# Face_PCB_Power___I2C.net
KiCad netlist of a schematic drawn in Altium Designer
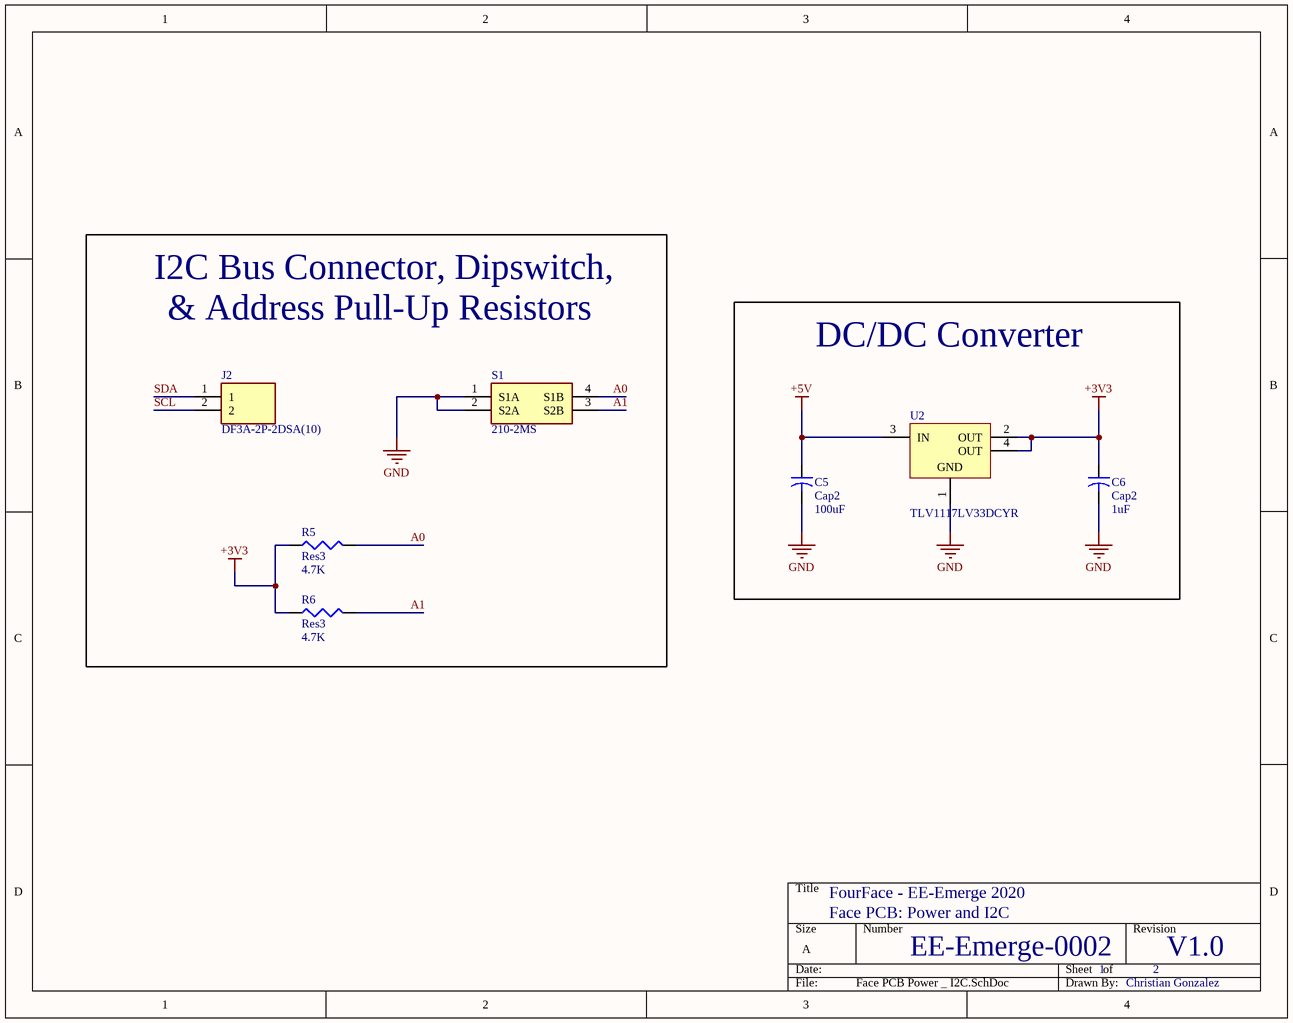
[diagram p0: Face PCB Power _ I2C.SchDoc]

(export (version "E")
  (design (tool "Eeschema 10.0.6"))
  (components
    (comp (ref "C5")
      (value "Cap2")
      (footprint "C0805")
      (description "Capacitor")
      (fields (field (name "ALTIUM_VALUE") "100uF") (field (name "PUBLISHER") "Altium Limited"))
      (libsource (lib "PCB_Project_2") (part "Cap2"))
    )
    (comp (ref "C6")
      (value "Cap2")
      (footprint "C0805")
      (description "Capacitor")
      (fields (field (name "ALTIUM_VALUE") "1uF") (field (name "PUBLISHER") "Altium Limited"))
      (libsource (lib "PCB_Project_2") (part "Cap2"))
    )
    (comp (ref "J2")
      (value "DF3A-2P-2DSA(10)")
      (footprint "SamacSys:SHDR2W50P0X200_1X2_600X500X500P")
      (description "Connector")
      (fields (field (name "MOUSER PART NUMBER") "798-DF3A-2P-2DSA10"))
      (libsource (lib "*") (part "DF3A-2P-2DSA(10)"))
    )
    (comp (ref "R5")
      (value "Res3")
      (footprint "6-0805_N")
      (description "Resistor")
      (fields (field (name "ALTIUM_VALUE") "4.7K") (field (name "PUBLISHER") "Altium Limited"))
      (libsource (lib "EE_Emerge_SkillsProject") (part "Res3"))
    )
    (comp (ref "R6")
      (value "Res3")
      (footprint "6-0805_N")
      (description "Resistor")
      (fields (field (name "ALTIUM_VALUE") "4.7K") (field (name "PUBLISHER") "Altium Limited"))
      (libsource (lib "EE_Emerge_SkillsProject") (part "Res3"))
    )
    (comp (ref "S1")
      (value "210-2MS")
      (footprint "SamacSys:DIP775W63P254L655H458Q4N")
      (description "Switch")
      (fields (field (name "MOUSER PART NUMBER") "774-2102MS") (field (name "RS PART NUMBER") "1774261"))
      (libsource (lib "*") (part "210-2MS"))
    )
    (comp (ref "U2")
      (value "TLV1117LV33DCYR")
      (footprint "DCY0004A_N")
      (fields (field (name "MANUFACTURER") "Texas Instruments"))
      (libsource (lib "Altium Content Vault") (part "TI-TLV1117LV33DCY4"))
    )
  )
  (nets
    (net (code "1") (name "+3V3") (class "Default")
      (node (ref "C6") (pin "1") (pinfunction "1_1") (pintype "passive"))
      (node (ref "R5") (pin "1") (pinfunction "1_1") (pintype "passive"))
      (node (ref "R6") (pin "1") (pinfunction "1_1") (pintype "passive"))
      (node (ref "U2") (pin "2") (pinfunction "OUT_2") (pintype "power_in"))
      (node (ref "U2") (pin "4") (pinfunction "OUT_4") (pintype "power_in"))
    )
    (net (code "2") (name "+5V") (class "Default")
      (node (ref "C5") (pin "1") (pinfunction "1_1") (pintype "passive"))
      (node (ref "U2") (pin "3") (pinfunction "IN_3") (pintype "power_in"))
    )
    (net (code "3") (name "/A0") (class "Default")
      (node (ref "R5") (pin "2") (pinfunction "2_2") (pintype "passive"))
      (node (ref "S1") (pin "4") (pinfunction "S1B_4") (pintype "passive"))
    )
    (net (code "4") (name "/A1") (class "Default")
      (node (ref "R6") (pin "2") (pinfunction "2_2") (pintype "passive"))
      (node (ref "S1") (pin "3") (pinfunction "S2B_3") (pintype "passive"))
    )
    (net (code "5") (name "/SCL") (class "Default")
      (node (ref "J2") (pin "2") (pinfunction "2_2") (pintype "passive"))
    )
    (net (code "6") (name "/SDA") (class "Default")
      (node (ref "J2") (pin "1") (pinfunction "1_1") (pintype "passive"))
    )
    (net (code "7") (name "GND") (class "Default")
      (node (ref "C5") (pin "2") (pinfunction "2_2") (pintype "passive"))
      (node (ref "C6") (pin "2") (pinfunction "2_2") (pintype "passive"))
      (node (ref "S1") (pin "1") (pinfunction "S1A_1") (pintype "passive"))
      (node (ref "S1") (pin "2") (pinfunction "S2A_2") (pintype "passive"))
      (node (ref "U2") (pin "1") (pinfunction "GND_1") (pintype "power_in"))
    )
  )
)
